# MUA08A_pac.net
KiCad netlist of a schematic drawn in EAGLE
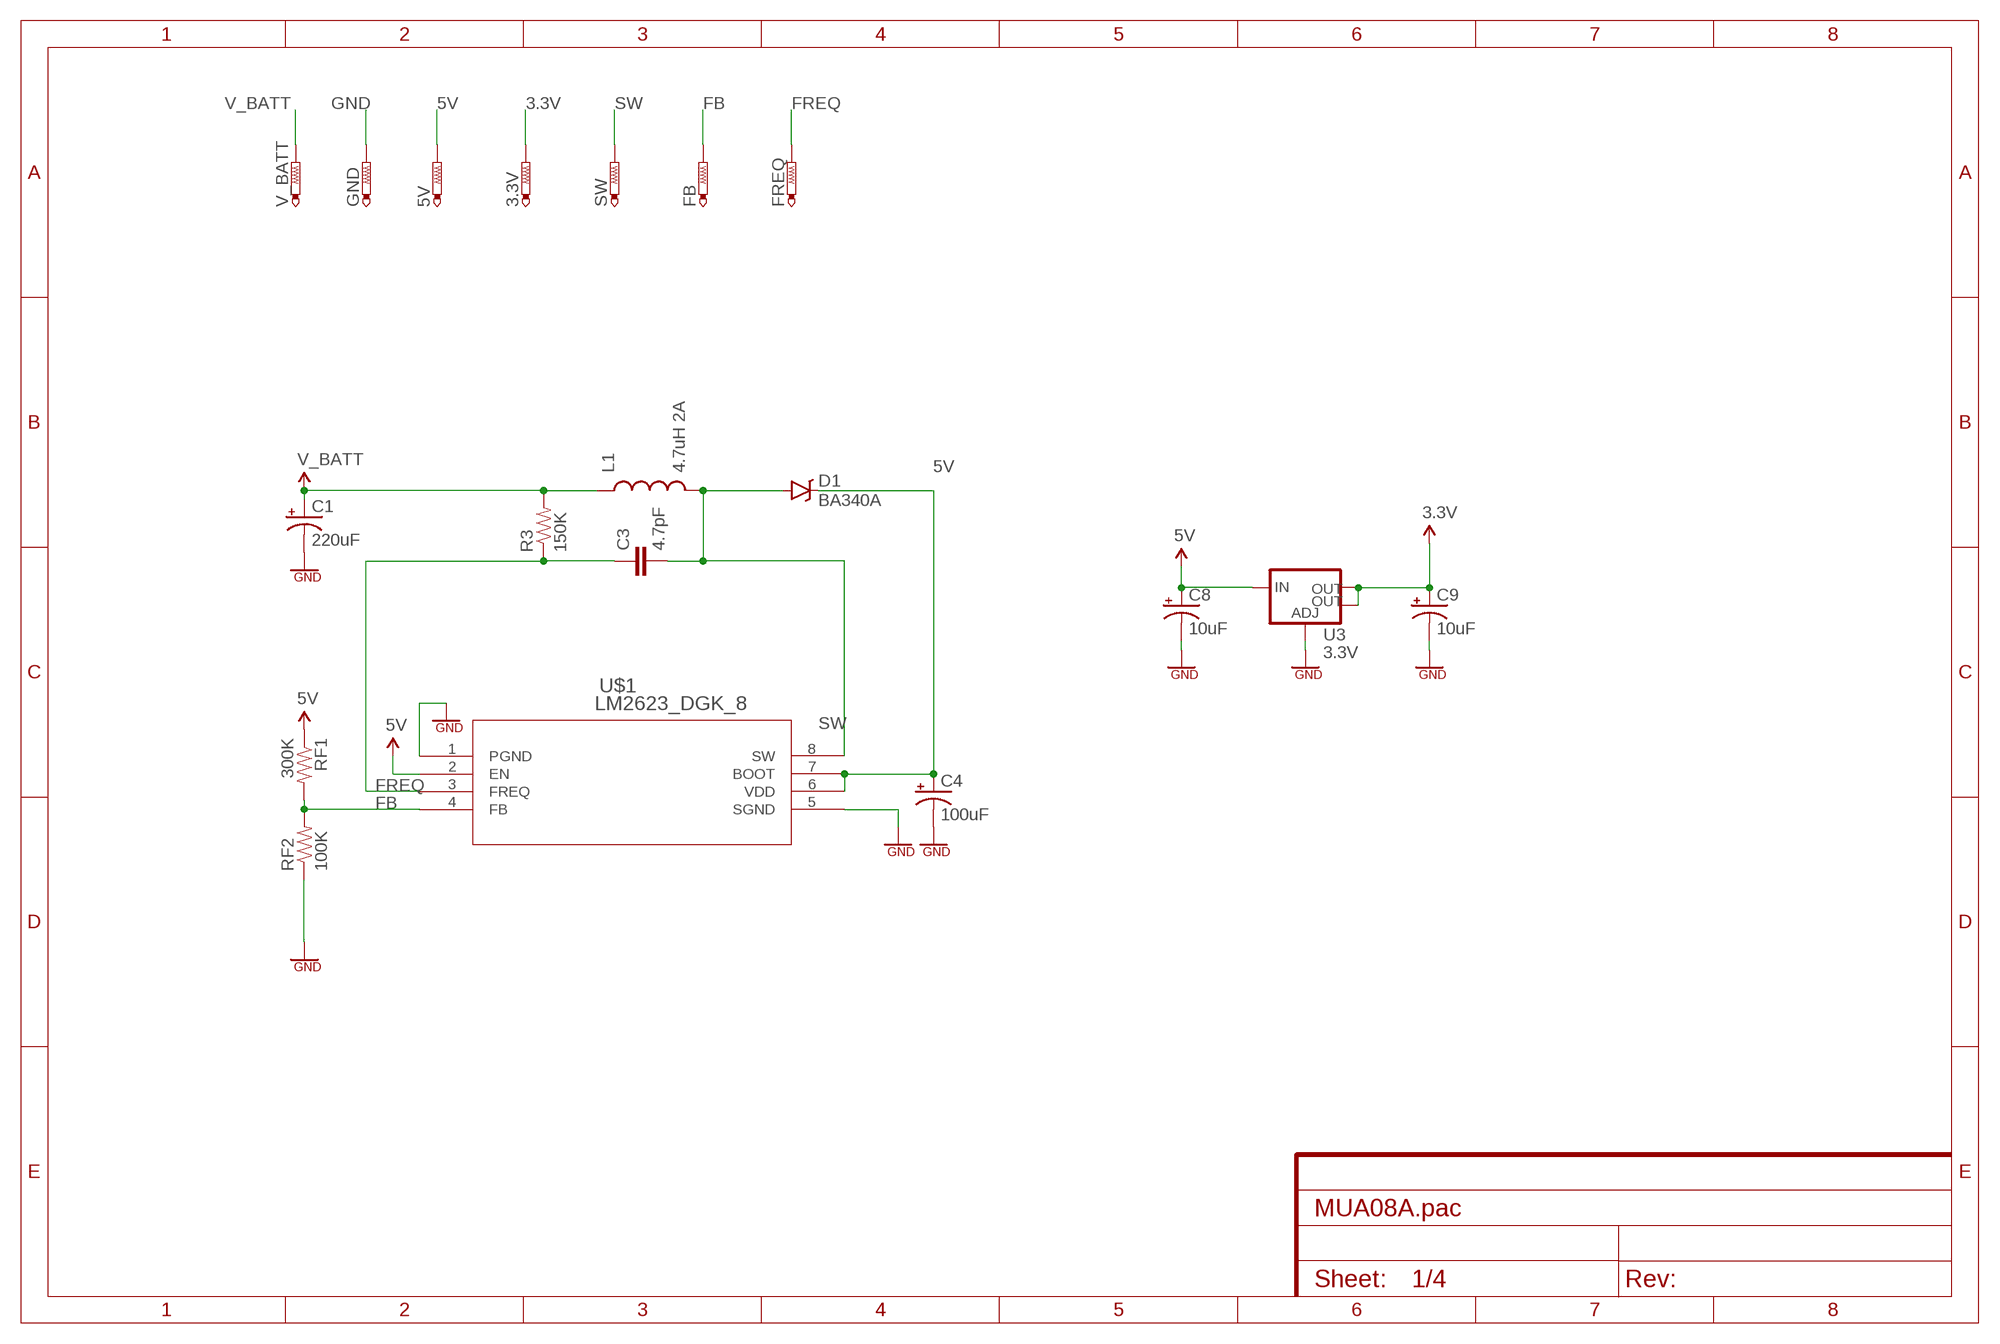
[diagram p0: schematic, sheet 1]
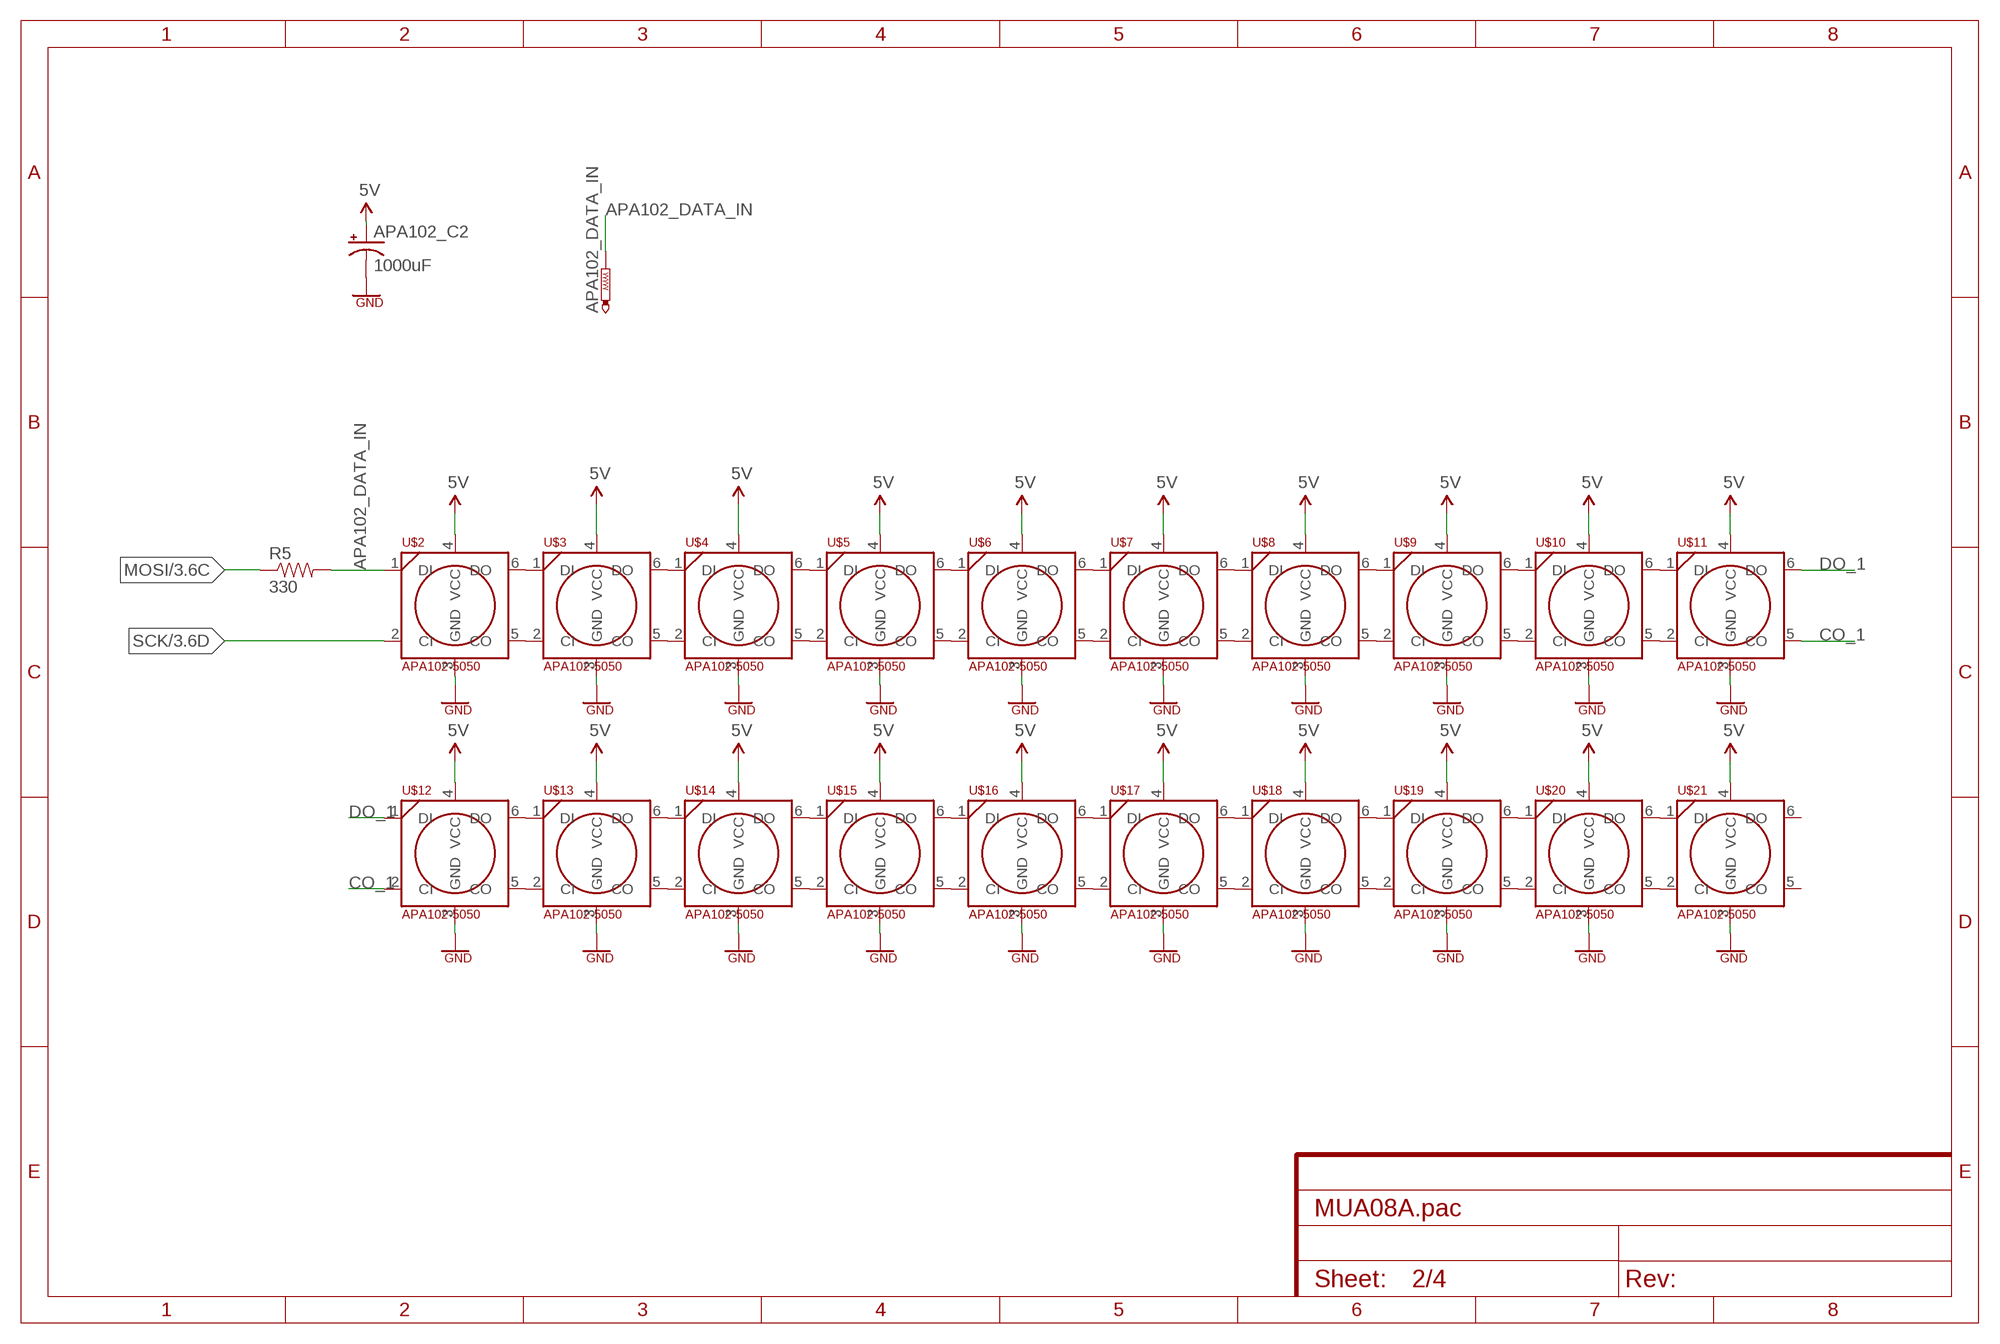
[diagram p1: schematic, sheet 2]
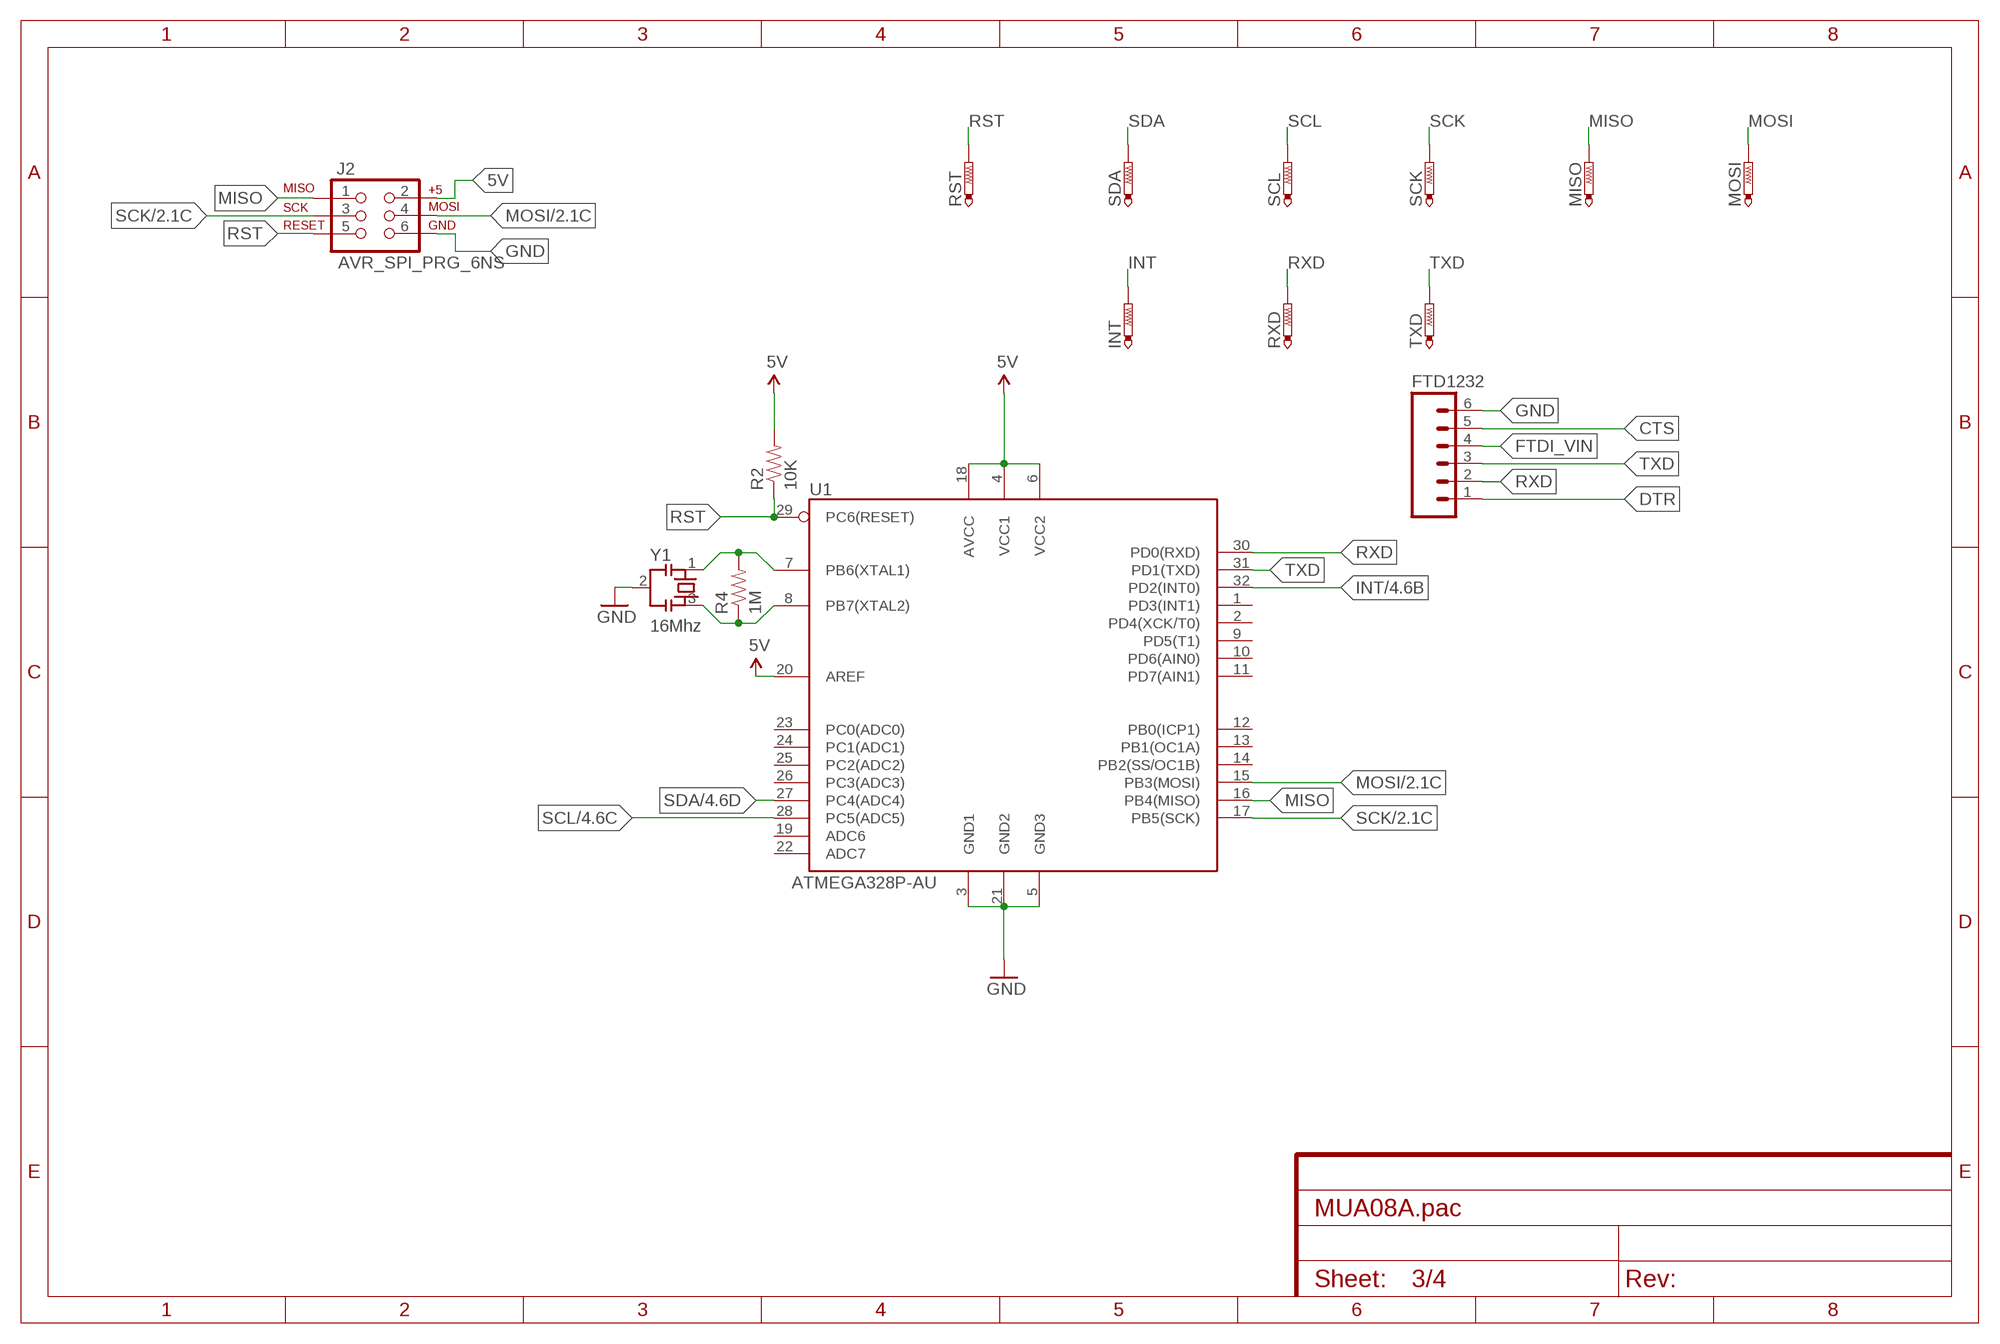
[diagram p2: schematic, sheet 3]
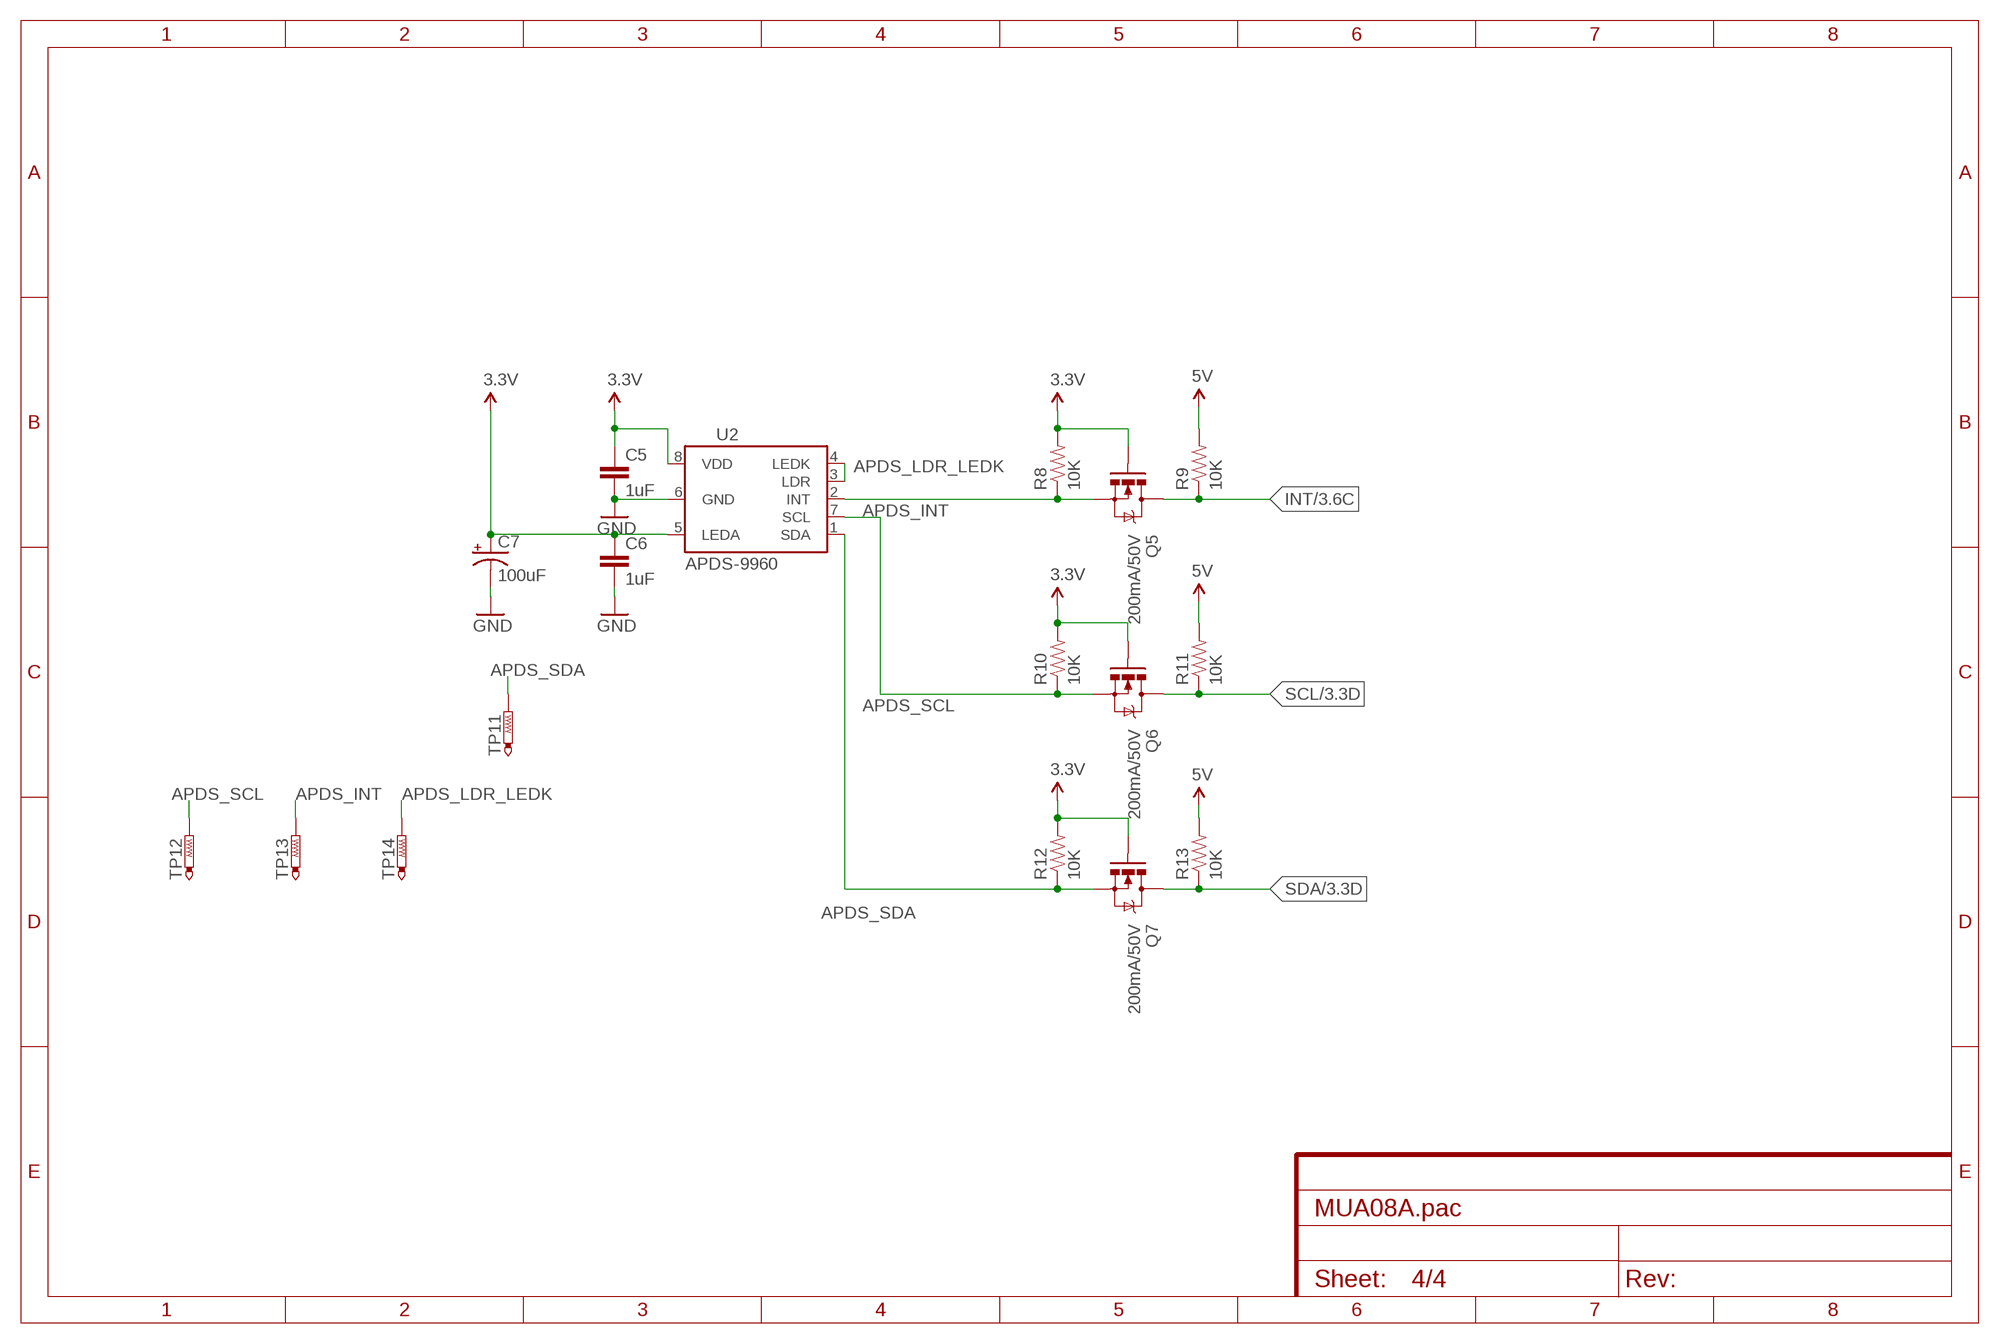
[diagram p3: schematic, sheet 4]

(export (version "E")
  (design (tool "Eeschema 10.0.6"))
  (components
    (comp (ref "3.3V")
      (value "PTR1PAD1-13")
      (footprint "eagle-import:P1-13")
      (libsource (lib "eagle-import") (part "PTR1PAD1-13"))
    )
    (comp (ref "5V")
      (value "PTR1PAD1-13")
      (footprint "eagle-import:P1-13")
      (libsource (lib "eagle-import") (part "PTR1PAD1-13"))
    )
    (comp (ref "C1")
      (value "220uF")
      (footprint "eagle-import:EIA3216-KIT")
      (libsource (lib "eagle-import") (part "CAP_POL1206-KIT"))
    )
    (comp (ref "C3")
      (value "4.7pF")
      (footprint "eagle-import:0603-CAP")
      (libsource (lib "eagle-import") (part "CAP0603-CAP"))
    )
    (comp (ref "C4")
      (value "100uF")
      (footprint "eagle-import:B_3528-21R")
      (libsource (lib "eagle-import") (part "CPOL-USB/3528-21R"))
    )
    (comp (ref "C8")
      (value "10uF")
      (footprint "eagle-import:EIA3216")
      (libsource (lib "eagle-import") (part "CAP_POL1206"))
    )
    (comp (ref "C9")
      (value "10uF")
      (footprint "eagle-import:EIA3216")
      (libsource (lib "eagle-import") (part "CAP_POL1206"))
    )
    (comp (ref "D1")
      (value "BA340A")
      (footprint "eagle-import:SMA-DIODE")
      (libsource (lib "eagle-import") (part "B340A"))
    )
    (comp (ref "FB")
      (value "PTR1PAD1-13")
      (footprint "eagle-import:P1-13")
      (libsource (lib "eagle-import") (part "PTR1PAD1-13"))
    )
    (comp (ref "FREQ")
      (value "PTR1PAD1-13")
      (footprint "eagle-import:P1-13")
      (libsource (lib "eagle-import") (part "PTR1PAD1-13"))
    )
    (comp (ref "GND")
      (value "PTR1PAD1-13")
      (footprint "eagle-import:P1-13")
      (libsource (lib "eagle-import") (part "PTR1PAD1-13"))
    )
    (comp (ref "L1")
      (value "4.7uH 2A")
      (footprint "eagle-import:CR54-KIT")
      (libsource (lib "eagle-import") (part "INDUCTORCR54-KIT"))
    )
    (comp (ref "R3")
      (value "150K")
      (footprint "eagle-import:0603-RES")
      (libsource (lib "eagle-import") (part "RESISTOR0603-RES"))
    )
    (comp (ref "RF1")
      (value "300K")
      (footprint "eagle-import:0603-RES")
      (libsource (lib "eagle-import") (part "RESISTOR0603-RES"))
    )
    (comp (ref "RF2")
      (value "100K")
      (footprint "eagle-import:0603-RES")
      (libsource (lib "eagle-import") (part "RESISTOR0603-RES"))
    )
    (comp (ref "SW")
      (value "PTR1PAD1-13")
      (footprint "eagle-import:P1-13")
      (libsource (lib "eagle-import") (part "PTR1PAD1-13"))
    )
    (comp (ref "U$1")
      (value "LM2623_DGK_8")
      (footprint "eagle-import:MUA08A")
      (fields (field (name "MANUFACTURER_PART_NUMBER") "lm2623ammnopb"))
      (libsource (lib "eagle-import") (part "LM2623_DGK_8"))
    )
    (comp (ref "U3")
      (value "3.3V")
      (footprint "eagle-import:SOT223")
      (libsource (lib "eagle-import") (part "V_REG_LM1117SOT223"))
    )
    (comp (ref "V_BATT")
      (value "PTR1PAD1-13")
      (footprint "eagle-import:P1-13")
      (libsource (lib "eagle-import") (part "PTR1PAD1-13"))
    )
    (comp (ref "FTD1232")
      (value "M06FEMALE_LOCK")
      (footprint "eagle-import:1X06_FEMALE_LOCK.010")
      (libsource (lib "eagle-import") (part "M06FEMALE_LOCK"))
    )
    (comp (ref "INT")
      (value "PTR1PAD1-13")
      (footprint "eagle-import:P1-13")
      (libsource (lib "eagle-import") (part "PTR1PAD1-13"))
    )
    (comp (ref "J2")
      (value "AVR_SPI_PRG_6NS")
      (footprint "eagle-import:2X3-NS")
      (libsource (lib "eagle-import") (part "AVR_SPI_PRG_6NS"))
    )
    (comp (ref "MISO")
      (value "PTR1PAD1-13")
      (footprint "eagle-import:P1-13")
      (libsource (lib "eagle-import") (part "PTR1PAD1-13"))
    )
    (comp (ref "MOSI")
      (value "PTR1PAD1-13")
      (footprint "eagle-import:P1-13")
      (libsource (lib "eagle-import") (part "PTR1PAD1-13"))
    )
    (comp (ref "R2")
      (value "10K")
      (footprint "eagle-import:0603-RES")
      (libsource (lib "eagle-import") (part "RESISTOR0603"))
    )
    (comp (ref "R4")
      (value "1M")
      (footprint "eagle-import:0603-RES")
      (libsource (lib "eagle-import") (part "RESISTOR0603"))
    )
    (comp (ref "RST")
      (value "PTR1PAD1-13")
      (footprint "eagle-import:P1-13")
      (libsource (lib "eagle-import") (part "PTR1PAD1-13"))
    )
    (comp (ref "RXD")
      (value "PTR1PAD1-13")
      (footprint "eagle-import:P1-13")
      (libsource (lib "eagle-import") (part "PTR1PAD1-13"))
    )
    (comp (ref "SCK")
      (value "PTR1PAD1-13")
      (footprint "eagle-import:P1-13")
      (libsource (lib "eagle-import") (part "PTR1PAD1-13"))
    )
    (comp (ref "SCL")
      (value "PTR1PAD1-13")
      (footprint "eagle-import:P1-13")
      (libsource (lib "eagle-import") (part "PTR1PAD1-13"))
    )
    (comp (ref "SDA")
      (value "PTR1PAD1-13")
      (footprint "eagle-import:P1-13")
      (libsource (lib "eagle-import") (part "PTR1PAD1-13"))
    )
    (comp (ref "TXD")
      (value "PTR1PAD1-13")
      (footprint "eagle-import:P1-13")
      (libsource (lib "eagle-import") (part "PTR1PAD1-13"))
    )
    (comp (ref "U1")
      (value "ATMEGA328P-AU")
      (footprint "eagle-import:TQFP32")
      (libsource (lib "eagle-import") (part "ATMEGA328P-AU"))
    )
    (comp (ref "Y1")
      (value "16Mhz")
      (footprint "eagle-import:CSTCE")
      (libsource (lib "eagle-import") (part "CSTCE"))
    )
    (comp (ref "APA102_C2")
      (value "1000uF")
      (footprint "eagle-import:D_7343-31W")
      (libsource (lib "eagle-import") (part "resistor_CPOL-USD/7343-31W"))
    )
    (comp (ref "APA102_DATA_IN")
      (value "PTR1PAD1-13")
      (footprint "eagle-import:P1-13")
      (libsource (lib "eagle-import") (part "PTR1PAD1-13"))
    )
    (comp (ref "R5")
      (value "330")
      (footprint "eagle-import:0603-RES")
      (libsource (lib "eagle-import") (part "RESISTOR0603-RES"))
    )
    (comp (ref "U$2")
      (value "APA102-5050")
      (footprint "eagle-import:5050")
      (libsource (lib "eagle-import") (part "APA102-5050"))
    )
    (comp (ref "U$3")
      (value "APA102-5050")
      (footprint "eagle-import:5050")
      (libsource (lib "eagle-import") (part "APA102-5050"))
    )
    (comp (ref "U$4")
      (value "APA102-5050")
      (footprint "eagle-import:5050")
      (libsource (lib "eagle-import") (part "APA102-5050"))
    )
    (comp (ref "U$5")
      (value "APA102-5050")
      (footprint "eagle-import:5050")
      (libsource (lib "eagle-import") (part "APA102-5050"))
    )
    (comp (ref "U$6")
      (value "APA102-5050")
      (footprint "eagle-import:5050")
      (libsource (lib "eagle-import") (part "APA102-5050"))
    )
    (comp (ref "U$7")
      (value "APA102-5050")
      (footprint "eagle-import:5050")
      (libsource (lib "eagle-import") (part "APA102-5050"))
    )
    (comp (ref "U$8")
      (value "APA102-5050")
      (footprint "eagle-import:5050")
      (libsource (lib "eagle-import") (part "APA102-5050"))
    )
    (comp (ref "U$9")
      (value "APA102-5050")
      (footprint "eagle-import:5050")
      (libsource (lib "eagle-import") (part "APA102-5050"))
    )
    (comp (ref "U$10")
      (value "APA102-5050")
      (footprint "eagle-import:5050")
      (libsource (lib "eagle-import") (part "APA102-5050"))
    )
    (comp (ref "U$11")
      (value "APA102-5050")
      (footprint "eagle-import:5050")
      (libsource (lib "eagle-import") (part "APA102-5050"))
    )
    (comp (ref "U$12")
      (value "APA102-5050")
      (footprint "eagle-import:5050")
      (libsource (lib "eagle-import") (part "APA102-5050"))
    )
    (comp (ref "U$13")
      (value "APA102-5050")
      (footprint "eagle-import:5050")
      (libsource (lib "eagle-import") (part "APA102-5050"))
    )
    (comp (ref "U$14")
      (value "APA102-5050")
      (footprint "eagle-import:5050")
      (libsource (lib "eagle-import") (part "APA102-5050"))
    )
    (comp (ref "U$15")
      (value "APA102-5050")
      (footprint "eagle-import:5050")
      (libsource (lib "eagle-import") (part "APA102-5050"))
    )
    (comp (ref "U$16")
      (value "APA102-5050")
      (footprint "eagle-import:5050")
      (libsource (lib "eagle-import") (part "APA102-5050"))
    )
    (comp (ref "U$17")
      (value "APA102-5050")
      (footprint "eagle-import:5050")
      (libsource (lib "eagle-import") (part "APA102-5050"))
    )
    (comp (ref "U$18")
      (value "APA102-5050")
      (footprint "eagle-import:5050")
      (libsource (lib "eagle-import") (part "APA102-5050"))
    )
    (comp (ref "U$19")
      (value "APA102-5050")
      (footprint "eagle-import:5050")
      (libsource (lib "eagle-import") (part "APA102-5050"))
    )
    (comp (ref "U$20")
      (value "APA102-5050")
      (footprint "eagle-import:5050")
      (libsource (lib "eagle-import") (part "APA102-5050"))
    )
    (comp (ref "U$21")
      (value "APA102-5050")
      (footprint "eagle-import:5050")
      (libsource (lib "eagle-import") (part "APA102-5050"))
    )
    (comp (ref "C5")
      (value "1uF")
      (footprint "eagle-import:0603-CAP")
      (libsource (lib "eagle-import") (part "SparkFun-Passives_CAP0603-CAP"))
    )
    (comp (ref "C6")
      (value "1uF")
      (footprint "eagle-import:0603-CAP")
      (libsource (lib "eagle-import") (part "SparkFun-Passives_CAP0603-CAP"))
    )
    (comp (ref "C7")
      (value "100uF")
      (footprint "eagle-import:EIA3216-KIT")
      (libsource (lib "eagle-import") (part "CAP_POL1206-KIT"))
    )
    (comp (ref "Q5")
      (value "200mA/50V")
      (footprint "eagle-import:SOT23-3")
      (libsource (lib "eagle-import") (part "MOSFET-NCHANNELBSS138"))
    )
    (comp (ref "Q6")
      (value "200mA/50V")
      (footprint "eagle-import:SOT23-3")
      (libsource (lib "eagle-import") (part "MOSFET-NCHANNELBSS138"))
    )
    (comp (ref "Q7")
      (value "200mA/50V")
      (footprint "eagle-import:SOT23-3")
      (libsource (lib "eagle-import") (part "MOSFET-NCHANNELBSS138"))
    )
    (comp (ref "R8")
      (value "10K")
      (footprint "eagle-import:0603-RES")
      (libsource (lib "eagle-import") (part "RESISTOR0603"))
    )
    (comp (ref "R9")
      (value "10K")
      (footprint "eagle-import:0603-RES")
      (libsource (lib "eagle-import") (part "RESISTOR0603"))
    )
    (comp (ref "R10")
      (value "10K")
      (footprint "eagle-import:0603-RES")
      (libsource (lib "eagle-import") (part "RESISTOR0603"))
    )
    (comp (ref "R11")
      (value "10K")
      (footprint "eagle-import:0603-RES")
      (libsource (lib "eagle-import") (part "RESISTOR0603"))
    )
    (comp (ref "R12")
      (value "10K")
      (footprint "eagle-import:0603-RES")
      (libsource (lib "eagle-import") (part "RESISTOR0603"))
    )
    (comp (ref "R13")
      (value "10K")
      (footprint "eagle-import:0603-RES")
      (libsource (lib "eagle-import") (part "RESISTOR0603"))
    )
    (comp (ref "TP11")
      (value "PTR1PAD1-13")
      (footprint "eagle-import:P1-13")
      (libsource (lib "eagle-import") (part "PTR1PAD1-13"))
    )
    (comp (ref "TP12")
      (value "PTR1PAD1-13")
      (footprint "eagle-import:P1-13")
      (libsource (lib "eagle-import") (part "PTR1PAD1-13"))
    )
    (comp (ref "TP13")
      (value "PTR1PAD1-13")
      (footprint "eagle-import:P1-13")
      (libsource (lib "eagle-import") (part "PTR1PAD1-13"))
    )
    (comp (ref "TP14")
      (value "PTR1PAD1-13")
      (footprint "eagle-import:P1-13")
      (libsource (lib "eagle-import") (part "PTR1PAD1-13"))
    )
    (comp (ref "U2")
      (value "APDS-9960")
      (footprint "eagle-import:APDS-9960")
      (libsource (lib "eagle-import") (part "APDS-9960"))
    )
  )
  (nets
    (net (code "1") (name "3.3V") (class "Default")
      (node (ref "3.3V") (pin "TP") (pinfunction "TP_TP") (pintype "input"))
      (node (ref "C5") (pin "1") (pinfunction "1_1") (pintype "passive"))
      (node (ref "C6") (pin "1") (pinfunction "1_1") (pintype "passive"))
      (node (ref "C7") (pin "A") (pinfunction "+_A") (pintype "passive"))
      (node (ref "C9") (pin "A") (pinfunction "+_A") (pintype "passive"))
      (node (ref "Q5") (pin "1") (pinfunction "G_1") (pintype "passive"))
      (node (ref "Q6") (pin "1") (pinfunction "G_1") (pintype "passive"))
      (node (ref "Q7") (pin "1") (pinfunction "G_1") (pintype "passive"))
      (node (ref "R10") (pin "2") (pinfunction "2_2") (pintype "passive"))
      (node (ref "R12") (pin "2") (pinfunction "2_2") (pintype "passive"))
      (node (ref "R8") (pin "2") (pinfunction "2_2") (pintype "passive"))
      (node (ref "U2") (pin "5") (pinfunction "LEDA_5") (pintype "bidirectional"))
      (node (ref "U2") (pin "8") (pinfunction "VDD_8") (pintype "bidirectional"))
      (node (ref "U3") (pin "2") (pinfunction "OUT_2") (pintype "output"))
      (node (ref "U3") (pin "4") (pinfunction "OUT_4") (pintype "output"))
    )
    (net (code "2") (name "5V") (class "Default")
      (node (ref "5V") (pin "TP") (pinfunction "TP_TP") (pintype "input"))
      (node (ref "APA102_C2") (pin "+") (pinfunction "+_+") (pintype "passive"))
      (node (ref "C4") (pin "+") (pinfunction "+_+") (pintype "passive"))
      (node (ref "C8") (pin "A") (pinfunction "+_A") (pintype "passive"))
      (node (ref "D1") (pin "C") (pinfunction "C_C") (pintype "passive"))
      (node (ref "J2") (pin "2") (pinfunction "2_2") (pintype "passive"))
      (node (ref "R11") (pin "2") (pinfunction "2_2") (pintype "passive"))
      (node (ref "R13") (pin "2") (pinfunction "2_2") (pintype "passive"))
      (node (ref "R2") (pin "2") (pinfunction "2_2") (pintype "passive"))
      (node (ref "R9") (pin "2") (pinfunction "2_2") (pintype "passive"))
      (node (ref "RF1") (pin "1") (pinfunction "1_1") (pintype "passive"))
      (node (ref "U$1") (pin "2") (pinfunction "EN_2") (pintype "input"))
      (node (ref "U$1") (pin "6") (pinfunction "VDD_6") (pintype "power_in"))
      (node (ref "U$1") (pin "7") (pinfunction "BOOT_7") (pintype "passive"))
      (node (ref "U$10") (pin "4") (pinfunction "VCC_4") (pintype "power_in"))
      (node (ref "U$11") (pin "4") (pinfunction "VCC_4") (pintype "power_in"))
      (node (ref "U$12") (pin "4") (pinfunction "VCC_4") (pintype "power_in"))
      (node (ref "U$13") (pin "4") (pinfunction "VCC_4") (pintype "power_in"))
      (node (ref "U$14") (pin "4") (pinfunction "VCC_4") (pintype "power_in"))
      (node (ref "U$15") (pin "4") (pinfunction "VCC_4") (pintype "power_in"))
      (node (ref "U$16") (pin "4") (pinfunction "VCC_4") (pintype "power_in"))
      (node (ref "U$17") (pin "4") (pinfunction "VCC_4") (pintype "power_in"))
      (node (ref "U$18") (pin "4") (pinfunction "VCC_4") (pintype "power_in"))
      (node (ref "U$19") (pin "4") (pinfunction "VCC_4") (pintype "power_in"))
      (node (ref "U$2") (pin "4") (pinfunction "VCC_4") (pintype "power_in"))
      (node (ref "U$20") (pin "4") (pinfunction "VCC_4") (pintype "power_in"))
      (node (ref "U$21") (pin "4") (pinfunction "VCC_4") (pintype "power_in"))
      (node (ref "U$3") (pin "4") (pinfunction "VCC_4") (pintype "power_in"))
      (node (ref "U$4") (pin "4") (pinfunction "VCC_4") (pintype "power_in"))
      (node (ref "U$5") (pin "4") (pinfunction "VCC_4") (pintype "power_in"))
      (node (ref "U$6") (pin "4") (pinfunction "VCC_4") (pintype "power_in"))
      (node (ref "U$7") (pin "4") (pinfunction "VCC_4") (pintype "power_in"))
      (node (ref "U$8") (pin "4") (pinfunction "VCC_4") (pintype "power_in"))
      (node (ref "U$9") (pin "4") (pinfunction "VCC_4") (pintype "power_in"))
      (node (ref "U1") (pin "18") (pinfunction "AVCC_18") (pintype "bidirectional"))
      (node (ref "U1") (pin "20") (pinfunction "AREF_20") (pintype "bidirectional"))
      (node (ref "U1") (pin "4") (pinfunction "VCC1_4") (pintype "bidirectional"))
      (node (ref "U1") (pin "6") (pinfunction "VCC2_6") (pintype "bidirectional"))
      (node (ref "U3") (pin "3") (pinfunction "IN_3") (pintype "input"))
    )
    (net (code "3") (name "APA102_DATA_IN") (class "Default")
      (node (ref "APA102_DATA_IN") (pin "TP") (pinfunction "TP_TP") (pintype "input"))
      (node (ref "R5") (pin "2") (pinfunction "2_2") (pintype "passive"))
      (node (ref "U$2") (pin "1") (pinfunction "DI_1") (pintype "input"))
    )
    (net (code "4") (name "APDS_INT") (class "Default")
      (node (ref "Q5") (pin "2") (pinfunction "S_2") (pintype "passive"))
      (node (ref "R8") (pin "1") (pinfunction "1_1") (pintype "passive"))
      (node (ref "TP13") (pin "TP") (pinfunction "TP_TP") (pintype "input"))
      (node (ref "U2") (pin "2") (pinfunction "INT_2") (pintype "bidirectional"))
    )
    (net (code "5") (name "APDS_LDR_LEDK") (class "Default")
      (node (ref "TP14") (pin "TP") (pinfunction "TP_TP") (pintype "input"))
      (node (ref "U2") (pin "3") (pinfunction "LDR_3") (pintype "bidirectional"))
      (node (ref "U2") (pin "4") (pinfunction "LEDK_4") (pintype "bidirectional"))
    )
    (net (code "6") (name "APDS_SCL") (class "Default")
      (node (ref "Q6") (pin "2") (pinfunction "S_2") (pintype "passive"))
      (node (ref "R10") (pin "1") (pinfunction "1_1") (pintype "passive"))
      (node (ref "TP12") (pin "TP") (pinfunction "TP_TP") (pintype "input"))
      (node (ref "U2") (pin "7") (pinfunction "SCL_7") (pintype "bidirectional"))
    )
    (net (code "7") (name "APDS_SDA") (class "Default")
      (node (ref "Q7") (pin "2") (pinfunction "S_2") (pintype "passive"))
      (node (ref "R12") (pin "1") (pinfunction "1_1") (pintype "passive"))
      (node (ref "TP11") (pin "TP") (pinfunction "TP_TP") (pintype "input"))
      (node (ref "U2") (pin "1") (pinfunction "SDA_1") (pintype "bidirectional"))
    )
    (net (code "8") (name "CO_1") (class "Default")
      (node (ref "U$11") (pin "5") (pinfunction "CO_5") (pintype "output"))
      (node (ref "U$12") (pin "2") (pinfunction "CI_2") (pintype "input"))
    )
    (net (code "9") (name "CTS") (class "Default")
      (node (ref "FTD1232") (pin "5") (pinfunction "5_5") (pintype "passive"))
    )
    (net (code "10") (name "DO_1") (class "Default")
      (node (ref "U$11") (pin "6") (pinfunction "DO_6") (pintype "output"))
      (node (ref "U$12") (pin "1") (pinfunction "DI_1") (pintype "input"))
    )
    (net (code "11") (name "DTR") (class "Default")
      (node (ref "FTD1232") (pin "1") (pinfunction "1_1") (pintype "passive"))
    )
    (net (code "12") (name "FB") (class "Default")
      (node (ref "FB") (pin "TP") (pinfunction "TP_TP") (pintype "input"))
      (node (ref "RF1") (pin "2") (pinfunction "2_2") (pintype "passive"))
      (node (ref "RF2") (pin "2") (pinfunction "2_2") (pintype "passive"))
      (node (ref "U$1") (pin "4") (pinfunction "FB_4") (pintype "input"))
    )
    (net (code "13") (name "FREQ") (class "Default")
      (node (ref "C3") (pin "1") (pinfunction "1_1") (pintype "passive"))
      (node (ref "FREQ") (pin "TP") (pinfunction "TP_TP") (pintype "input"))
      (node (ref "R3") (pin "1") (pinfunction "1_1") (pintype "passive"))
      (node (ref "U$1") (pin "3") (pinfunction "FREQ_3") (pintype "input"))
    )
    (net (code "14") (name "FTDI_VIN") (class "Default")
      (node (ref "FTD1232") (pin "4") (pinfunction "4_4") (pintype "passive"))
    )
    (net (code "15") (name "GND") (class "Default")
      (node (ref "APA102_C2") (pin "-") (pinfunction "-_-") (pintype "passive"))
      (node (ref "C1") (pin "C") (pinfunction "-_C") (pintype "passive"))
      (node (ref "C4") (pin "-") (pinfunction "-_-") (pintype "passive"))
      (node (ref "C5") (pin "2") (pinfunction "2_2") (pintype "passive"))
      (node (ref "C6") (pin "2") (pinfunction "2_2") (pintype "passive"))
      (node (ref "C7") (pin "C") (pinfunction "-_C") (pintype "passive"))
      (node (ref "C8") (pin "C") (pinfunction "-_C") (pintype "passive"))
      (node (ref "C9") (pin "C") (pinfunction "-_C") (pintype "passive"))
      (node (ref "FTD1232") (pin "6") (pinfunction "6_6") (pintype "passive"))
      (node (ref "GND") (pin "TP") (pinfunction "TP_TP") (pintype "input"))
      (node (ref "J2") (pin "6") (pinfunction "6_6") (pintype "passive"))
      (node (ref "RF2") (pin "1") (pinfunction "1_1") (pintype "passive"))
      (node (ref "U$1") (pin "1") (pinfunction "PGND_1") (pintype "power_in"))
      (node (ref "U$1") (pin "5") (pinfunction "SGND_5") (pintype "power_in"))
      (node (ref "U$10") (pin "3") (pinfunction "GND_3") (pintype "power_in"))
      (node (ref "U$11") (pin "3") (pinfunction "GND_3") (pintype "power_in"))
      (node (ref "U$12") (pin "3") (pinfunction "GND_3") (pintype "power_in"))
      (node (ref "U$13") (pin "3") (pinfunction "GND_3") (pintype "power_in"))
      (node (ref "U$14") (pin "3") (pinfunction "GND_3") (pintype "power_in"))
      (node (ref "U$15") (pin "3") (pinfunction "GND_3") (pintype "power_in"))
      (node (ref "U$16") (pin "3") (pinfunction "GND_3") (pintype "power_in"))
      (node (ref "U$17") (pin "3") (pinfunction "GND_3") (pintype "power_in"))
      (node (ref "U$18") (pin "3") (pinfunction "GND_3") (pintype "power_in"))
      (node (ref "U$19") (pin "3") (pinfunction "GND_3") (pintype "power_in"))
      (node (ref "U$2") (pin "3") (pinfunction "GND_3") (pintype "power_in"))
      (node (ref "U$20") (pin "3") (pinfunction "GND_3") (pintype "power_in"))
      (node (ref "U$21") (pin "3") (pinfunction "GND_3") (pintype "power_in"))
      (node (ref "U$3") (pin "3") (pinfunction "GND_3") (pintype "power_in"))
      (node (ref "U$4") (pin "3") (pinfunction "GND_3") (pintype "power_in"))
      (node (ref "U$5") (pin "3") (pinfunction "GND_3") (pintype "power_in"))
      (node (ref "U$6") (pin "3") (pinfunction "GND_3") (pintype "power_in"))
      (node (ref "U$7") (pin "3") (pinfunction "GND_3") (pintype "power_in"))
      (node (ref "U$8") (pin "3") (pinfunction "GND_3") (pintype "power_in"))
      (node (ref "U$9") (pin "3") (pinfunction "GND_3") (pintype "power_in"))
      (node (ref "U1") (pin "21") (pinfunction "GND2_21") (pintype "bidirectional"))
      (node (ref "U1") (pin "3") (pinfunction "GND1_3") (pintype "bidirectional"))
      (node (ref "U1") (pin "5") (pinfunction "GND3_5") (pintype "bidirectional"))
      (node (ref "U2") (pin "6") (pinfunction "GND_6") (pintype "bidirectional"))
      (node (ref "U3") (pin "1") (pinfunction "ADJ_1") (pintype "input"))
      (node (ref "Y1") (pin "2") (pinfunction "2_2") (pintype "passive"))
    )
    (net (code "16") (name "INT") (class "Default")
      (node (ref "INT") (pin "TP") (pinfunction "TP_TP") (pintype "input"))
      (node (ref "Q5") (pin "3") (pinfunction "D_3") (pintype "passive"))
      (node (ref "R9") (pin "1") (pinfunction "1_1") (pintype "passive"))
      (node (ref "U1") (pin "32") (pinfunction "PD2(INT0)_32") (pintype "bidirectional"))
    )
    (net (code "17") (name "MISO") (class "Default")
      (node (ref "J2") (pin "1") (pinfunction "1_1") (pintype "passive"))
      (node (ref "MISO") (pin "TP") (pinfunction "TP_TP") (pintype "input"))
      (node (ref "U1") (pin "16") (pinfunction "PB4(MISO)_16") (pintype "bidirectional"))
    )
    (net (code "18") (name "MOSI") (class "Default")
      (node (ref "J2") (pin "4") (pinfunction "4_4") (pintype "passive"))
      (node (ref "MOSI") (pin "TP") (pinfunction "TP_TP") (pintype "input"))
      (node (ref "R5") (pin "1") (pinfunction "1_1") (pintype "passive"))
      (node (ref "U1") (pin "15") (pinfunction "PB3(MOSI)_15") (pintype "bidirectional"))
    )
    (net (code "19") (name "Net-(U$2-CO)") (class "Default")
      (node (ref "U$2") (pin "5") (pinfunction "CO_5") (pintype "output"))
      (node (ref "U$3") (pin "2") (pinfunction "CI_2") (pintype "input"))
    )
    (net (code "20") (name "Net-(U$2-DO)") (class "Default")
      (node (ref "U$2") (pin "6") (pinfunction "DO_6") (pintype "output"))
      (node (ref "U$3") (pin "1") (pinfunction "DI_1") (pintype "input"))
    )
    (net (code "21") (name "Net-(U$3-CO)") (class "Default")
      (node (ref "U$3") (pin "5") (pinfunction "CO_5") (pintype "output"))
      (node (ref "U$4") (pin "2") (pinfunction "CI_2") (pintype "input"))
    )
    (net (code "22") (name "Net-(U$3-DO)") (class "Default")
      (node (ref "U$3") (pin "6") (pinfunction "DO_6") (pintype "output"))
      (node (ref "U$4") (pin "1") (pinfunction "DI_1") (pintype "input"))
    )
    (net (code "23") (name "Net-(U$4-CO)") (class "Default")
      (node (ref "U$4") (pin "5") (pinfunction "CO_5") (pintype "output"))
      (node (ref "U$5") (pin "2") (pinfunction "CI_2") (pintype "input"))
    )
    (net (code "24") (name "Net-(U$4-DO)") (class "Default")
      (node (ref "U$4") (pin "6") (pinfunction "DO_6") (pintype "output"))
      (node (ref "U$5") (pin "1") (pinfunction "DI_1") (pintype "input"))
    )
    (net (code "25") (name "Net-(U$5-CO)") (class "Default")
      (node (ref "U$5") (pin "5") (pinfunction "CO_5") (pintype "output"))
      (node (ref "U$6") (pin "2") (pinfunction "CI_2") (pintype "input"))
    )
    (net (code "26") (name "Net-(U$5-DO)") (class "Default")
      (node (ref "U$5") (pin "6") (pinfunction "DO_6") (pintype "output"))
      (node (ref "U$6") (pin "1") (pinfunction "DI_1") (pintype "input"))
    )
    (net (code "27") (name "Net-(U$6-CO)") (class "Default")
      (node (ref "U$6") (pin "5") (pinfunction "CO_5") (pintype "output"))
      (node (ref "U$7") (pin "2") (pinfunction "CI_2") (pintype "input"))
    )
    (net (code "28") (name "Net-(U$6-DO)") (class "Default")
      (node (ref "U$6") (pin "6") (pinfunction "DO_6") (pintype "output"))
      (node (ref "U$7") (pin "1") (pinfunction "DI_1") (pintype "input"))
    )
    (net (code "29") (name "Net-(U$7-CO)") (class "Default")
      (node (ref "U$7") (pin "5") (pinfunction "CO_5") (pintype "output"))
      (node (ref "U$8") (pin "2") (pinfunction "CI_2") (pintype "input"))
    )
    (net (code "30") (name "Net-(U$7-DO)") (class "Default")
      (node (ref "U$7") (pin "6") (pinfunction "DO_6") (pintype "output"))
      (node (ref "U$8") (pin "1") (pinfunction "DI_1") (pintype "input"))
    )
    (net (code "31") (name "Net-(U$8-CO)") (class "Default")
      (node (ref "U$8") (pin "5") (pinfunction "CO_5") (pintype "output"))
      (node (ref "U$9") (pin "2") (pinfunction "CI_2") (pintype "input"))
    )
    (net (code "32") (name "Net-(U$8-DO)") (class "Default")
      (node (ref "U$8") (pin "6") (pinfunction "DO_6") (pintype "output"))
      (node (ref "U$9") (pin "1") (pinfunction "DI_1") (pintype "input"))
    )
    (net (code "33") (name "Net-(U$10-CI)") (class "Default")
      (node (ref "U$10") (pin "2") (pinfunction "CI_2") (pintype "input"))
      (node (ref "U$9") (pin "5") (pinfunction "CO_5") (pintype "output"))
    )
    (net (code "34") (name "Net-(U$10-CO)") (class "Default")
      (node (ref "U$10") (pin "5") (pinfunction "CO_5") (pintype "output"))
      (node (ref "U$11") (pin "2") (pinfunction "CI_2") (pintype "input"))
    )
    (net (code "35") (name "Net-(U$10-DI)") (class "Default")
      (node (ref "U$10") (pin "1") (pinfunction "DI_1") (pintype "input"))
      (node (ref "U$9") (pin "6") (pinfunction "DO_6") (pintype "output"))
    )
    (net (code "36") (name "Net-(U$10-DO)") (class "Default")
      (node (ref "U$10") (pin "6") (pinfunction "DO_6") (pintype "output"))
      (node (ref "U$11") (pin "1") (pinfunction "DI_1") (pintype "input"))
    )
    (net (code "37") (name "Net-(U$12-CO)") (class "Default")
      (node (ref "U$12") (pin "5") (pinfunction "CO_5") (pintype "output"))
      (node (ref "U$13") (pin "2") (pinfunction "CI_2") (pintype "input"))
    )
    (net (code "38") (name "Net-(U$12-DO)") (class "Default")
      (node (ref "U$12") (pin "6") (pinfunction "DO_6") (pintype "output"))
      (node (ref "U$13") (pin "1") (pinfunction "DI_1") (pintype "input"))
    )
    (net (code "39") (name "Net-(U$13-CO)") (class "Default")
      (node (ref "U$13") (pin "5") (pinfunction "CO_5") (pintype "output"))
      (node (ref "U$14") (pin "2") (pinfunction "CI_2") (pintype "input"))
    )
    (net (code "40") (name "Net-(U$13-DO)") (class "Default")
      (node (ref "U$13") (pin "6") (pinfunction "DO_6") (pintype "output"))
      (node (ref "U$14") (pin "1") (pinfunction "DI_1") (pintype "input"))
    )
    (net (code "41") (name "Net-(U$14-CO)") (class "Default")
      (node (ref "U$14") (pin "5") (pinfunction "CO_5") (pintype "output"))
      (node (ref "U$15") (pin "2") (pinfunction "CI_2") (pintype "input"))
    )
    (net (code "42") (name "Net-(U$14-DO)") (class "Default")
      (node (ref "U$14") (pin "6") (pinfunction "DO_6") (pintype "output"))
      (node (ref "U$15") (pin "1") (pinfunction "DI_1") (pintype "input"))
    )
    (net (code "43") (name "Net-(U$15-CO)") (class "Default")
      (node (ref "U$15") (pin "5") (pinfunction "CO_5") (pintype "output"))
      (node (ref "U$16") (pin "2") (pinfunction "CI_2") (pintype "input"))
    )
    (net (code "44") (name "Net-(U$15-DO)") (class "Default")
      (node (ref "U$15") (pin "6") (pinfunction "DO_6") (pintype "output"))
      (node (ref "U$16") (pin "1") (pinfunction "DI_1") (pintype "input"))
    )
    (net (code "45") (name "Net-(U$16-CO)") (class "Default")
      (node (ref "U$16") (pin "5") (pinfunction "CO_5") (pintype "output"))
      (node (ref "U$17") (pin "2") (pinfunction "CI_2") (pintype "input"))
    )
    (net (code "46") (name "Net-(U$16-DO)") (class "Default")
      (node (ref "U$16") (pin "6") (pinfunction "DO_6") (pintype "output"))
      (node (ref "U$17") (pin "1") (pinfunction "DI_1") (pintype "input"))
    )
    (net (code "47") (name "Net-(U$17-CO)") (class "Default")
      (node (ref "U$17") (pin "5") (pinfunction "CO_5") (pintype "output"))
      (node (ref "U$18") (pin "2") (pinfunction "CI_2") (pintype "input"))
    )
    (net (code "48") (name "Net-(U$17-DO)") (class "Default")
      (node (ref "U$17") (pin "6") (pinfunction "DO_6") (pintype "output"))
      (node (ref "U$18") (pin "1") (pinfunction "DI_1") (pintype "input"))
    )
    (net (code "49") (name "Net-(U$18-CO)") (class "Default")
      (node (ref "U$18") (pin "5") (pinfunction "CO_5") (pintype "output"))
      (node (ref "U$19") (pin "2") (pinfunction "CI_2") (pintype "input"))
    )
    (net (code "50") (name "Net-(U$18-DO)") (class "Default")
      (node (ref "U$18") (pin "6") (pinfunction "DO_6") (pintype "output"))
      (node (ref "U$19") (pin "1") (pinfunction "DI_1") (pintype "input"))
    )
    (net (code "51") (name "Net-(U$19-CO)") (class "Default")
      (node (ref "U$19") (pin "5") (pinfunction "CO_5") (pintype "output"))
      (node (ref "U$20") (pin "2") (pinfunction "CI_2") (pintype "input"))
    )
    (net (code "52") (name "Net-(U$19-DO)") (class "Default")
      (node (ref "U$19") (pin "6") (pinfunction "DO_6") (pintype "output"))
      (node (ref "U$20") (pin "1") (pinfunction "DI_1") (pintype "input"))
    )
    (net (code "53") (name "Net-(U$20-CO)") (class "Default")
      (node (ref "U$20") (pin "5") (pinfunction "CO_5") (pintype "output"))
      (node (ref "U$21") (pin "2") (pinfunction "CI_2") (pintype "input"))
    )
    (net (code "54") (name "Net-(U$20-DO)") (class "Default")
      (node (ref "U$20") (pin "6") (pinfunction "DO_6") (pintype "output"))
      (node (ref "U$21") (pin "1") (pinfunction "DI_1") (pintype "input"))
    )
    (net (code "55") (name "Net-(U1-PB6(XTAL1))") (class "Default")
      (node (ref "R4") (pin "2") (pinfunction "2_2") (pintype "passive"))
      (node (ref "U1") (pin "7") (pinfunction "PB6(XTAL1)_7") (pintype "bidirectional"))
      (node (ref "Y1") (pin "1") (pinfunction "1_1") (pintype "passive"))
    )
    (net (code "56") (name "Net-(U1-PB7(XTAL2))") (class "Default")
      (node (ref "R4") (pin "1") (pinfunction "1_1") (pintype "passive"))
      (node (ref "U1") (pin "8") (pinfunction "PB7(XTAL2)_8") (pintype "bidirectional"))
      (node (ref "Y1") (pin "3") (pinfunction "3_3") (pintype "passive"))
    )
    (net (code "57") (name "RST") (class "Default")
      (node (ref "J2") (pin "5") (pinfunction "5_5") (pintype "passive"))
      (node (ref "R2") (pin "1") (pinfunction "1_1") (pintype "passive"))
      (node (ref "RST") (pin "TP") (pinfunction "TP_TP") (pintype "input"))
      (node (ref "U1") (pin "29") (pinfunction "PC6(RESET)_29") (pintype "bidirectional"))
    )
    (net (code "58") (name "RXD") (class "Default")
      (node (ref "FTD1232") (pin "2") (pinfunction "2_2") (pintype "passive"))
      (node (ref "RXD") (pin "TP") (pinfunction "TP_TP") (pintype "input"))
      (node (ref "U1") (pin "30") (pinfunction "PD0(RXD)_30") (pintype "bidirectional"))
    )
    (net (code "59") (name "SCK") (class "Default")
      (node (ref "J2") (pin "3") (pinfunction "3_3") (pintype "passive"))
      (node (ref "SCK") (pin "TP") (pinfunction "TP_TP") (pintype "input"))
      (node (ref "U$2") (pin "2") (pinfunction "CI_2") (pintype "input"))
      (node (ref "U1") (pin "17") (pinfunction "PB5(SCK)_17") (pintype "bidirectional"))
    )
    (net (code "60") (name "SCL") (class "Default")
      (node (ref "Q6") (pin "3") (pinfunction "D_3") (pintype "passive"))
      (node (ref "R11") (pin "1") (pinfunction "1_1") (pintype "passive"))
      (node (ref "SCL") (pin "TP") (pinfunction "TP_TP") (pintype "input"))
      (node (ref "U1") (pin "28") (pinfunction "PC5(ADC5)_28") (pintype "bidirectional"))
    )
    (net (code "61") (name "SDA") (class "Default")
      (node (ref "Q7") (pin "3") (pinfunction "D_3") (pintype "passive"))
      (node (ref "R13") (pin "1") (pinfunction "1_1") (pintype "passive"))
      (node (ref "SDA") (pin "TP") (pinfunction "TP_TP") (pintype "input"))
      (node (ref "U1") (pin "27") (pinfunction "PC4(ADC4)_27") (pintype "bidirectional"))
    )
    (net (code "62") (name "SW") (class "Default")
      (node (ref "C3") (pin "2") (pinfunction "2_2") (pintype "passive"))
      (node (ref "D1") (pin "A") (pinfunction "A_A") (pintype "passive"))
      (node (ref "L1") (pin "P$2") (pinfunction "2_P$2") (pintype "passive"))
      (node (ref "SW") (pin "TP") (pinfunction "TP_TP") (pintype "input"))
      (node (ref "U$1") (pin "8") (pinfunction "SW_8") (pintype "passive"))
    )
    (net (code "63") (name "TXD") (class "Default")
      (node (ref "FTD1232") (pin "3") (pinfunction "3_3") (pintype "passive"))
      (node (ref "TXD") (pin "TP") (pinfunction "TP_TP") (pintype "input"))
      (node (ref "U1") (pin "31") (pinfunction "PD1(TXD)_31") (pintype "bidirectional"))
    )
    (net (code "64") (name "V_BATT") (class "Default")
      (node (ref "C1") (pin "A") (pinfunction "+_A") (pintype "passive"))
      (node (ref "L1") (pin "P$1") (pinfunction "1_P$1") (pintype "passive"))
      (node (ref "R3") (pin "2") (pinfunction "2_2") (pintype "passive"))
      (node (ref "V_BATT") (pin "TP") (pinfunction "TP_TP") (pintype "input"))
    )
    (net (code "65") (name "unconnected-(U$21-CO-Pad5)") (class "Default")
      (node (ref "U$21") (pin "5") (pinfunction "CO_5") (pintype "output"))
    )
    (net (code "66") (name "unconnected-(U$21-DO-Pad6)") (class "Default")
      (node (ref "U$21") (pin "6") (pinfunction "DO_6") (pintype "output"))
    )
    (net (code "67") (name "unconnected-(U1-ADC6-Pad19)") (class "Default")
      (node (ref "U1") (pin "19") (pinfunction "ADC6_19") (pintype "bidirectional"))
    )
    (net (code "68") (name "unconnected-(U1-ADC7-Pad22)") (class "Default")
      (node (ref "U1") (pin "22") (pinfunction "ADC7_22") (pintype "bidirectional"))
    )
    (net (code "69") (name "unconnected-(U1-PB0(ICP1)-Pad12)") (class "Default")
      (node (ref "U1") (pin "12") (pinfunction "PB0(ICP1)_12") (pintype "bidirectional"))
    )
    (net (code "70") (name "unconnected-(U1-PB1(OC1A)-Pad13)") (class "Default")
      (node (ref "U1") (pin "13") (pinfunction "PB1(OC1A)_13") (pintype "bidirectional"))
    )
    (net (code "71") (name "unconnected-(U1-PB2(SS{slash}OC1B)-Pad14)") (class "Default")
      (node (ref "U1") (pin "14") (pinfunction "PB2(SS/OC1B)_14") (pintype "bidirectional"))
    )
    (net (code "72") (name "unconnected-(U1-PC0(ADC0)-Pad23)") (class "Default")
      (node (ref "U1") (pin "23") (pinfunction "PC0(ADC0)_23") (pintype "bidirectional"))
    )
    (net (code "73") (name "unconnected-(U1-PC1(ADC1)-Pad24)") (class "Default")
      (node (ref "U1") (pin "24") (pinfunction "PC1(ADC1)_24") (pintype "bidirectional"))
    )
    (net (code "74") (name "unconnected-(U1-PC2(ADC2)-Pad25)") (class "Default")
      (node (ref "U1") (pin "25") (pinfunction "PC2(ADC2)_25") (pintype "bidirectional"))
    )
    (net (code "75") (name "unconnected-(U1-PC3(ADC3)-Pad26)") (class "Default")
      (node (ref "U1") (pin "26") (pinfunction "PC3(ADC3)_26") (pintype "bidirectional"))
    )
    (net (code "76") (name "unconnected-(U1-PD3(INT1)-Pad1)") (class "Default")
      (node (ref "U1") (pin "1") (pinfunction "PD3(INT1)_1") (pintype "bidirectional"))
    )
    (net (code "77") (name "unconnected-(U1-PD4(XCK{slash}T0)-Pad2)") (class "Default")
      (node (ref "U1") (pin "2") (pinfunction "PD4(XCK/T0)_2") (pintype "bidirectional"))
    )
    (net (code "78") (name "unconnected-(U1-PD5(T1)-Pad9)") (class "Default")
      (node (ref "U1") (pin "9") (pinfunction "PD5(T1)_9") (pintype "bidirectional"))
    )
    (net (code "79") (name "unconnected-(U1-PD6(AIN0)-Pad10)") (class "Default")
      (node (ref "U1") (pin "10") (pinfunction "PD6(AIN0)_10") (pintype "bidirectional"))
    )
    (net (code "80") (name "unconnected-(U1-PD7(AIN1)-Pad11)") (class "Default")
      (node (ref "U1") (pin "11") (pinfunction "PD7(AIN1)_11") (pintype "bidirectional"))
    )
  )
)
